# MCU_Signals.net
KiCad netlist of a schematic drawn in Altium Designer
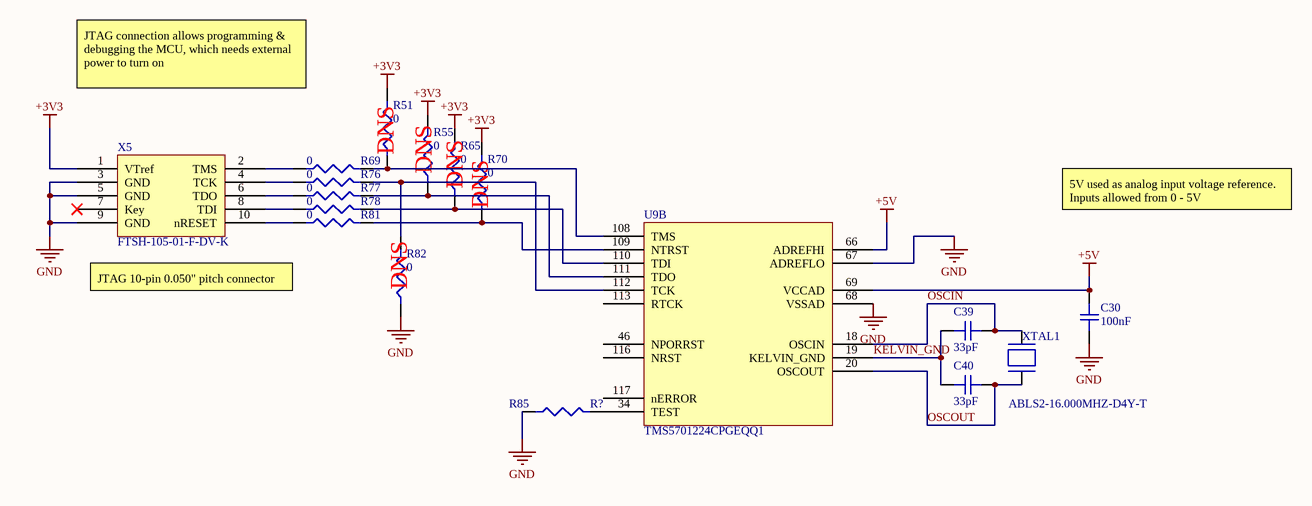
[diagram p0: MCU_Signals.SchDoc]

(export (version "E")
  (design (tool "Eeschema 10.0.6"))
  (components
    (comp (ref "C30")
      (value "100nF")
      (footprint "PHANTOM_FOOTPRINTS:C0805")
      (description "MLCC SMD CAP 100nF 10Volts U2J 5%")
      (fields
        (field (name "MANUFACTURER") "Murata")
        (field (name "MANUFACTURER PART NUMBER") "GRM21B7U1A104JA01L")
      )
      (libsource (lib "PHANTOM_LIBRARY") (part "GRM21B7U1A104JA01L"))
    )
    (comp (ref "C39")
      (value "33pF")
      (footprint "C0805")
      (description "33pF 10V Ceramic Capacitor C0G, NP0 0805 (2012 Metric) 0.079\" L x 0.049\" W (2.00mm x 1.25mm)")
      (fields
        (field (name "MANUFACTURER") "Wurth Electronics")
        (field (name "MANUFACTURER PART NUMBER") "885012007003")
      )
      (libsource (lib "PHANTOM_LIBRARY") (part "885012007003"))
    )
    (comp (ref "C40")
      (value "33pF")
      (footprint "C0805")
      (description "33pF 10V Ceramic Capacitor C0G, NP0 0805 (2012 Metric) 0.079\" L x 0.049\" W (2.00mm x 1.25mm)")
      (fields
        (field (name "MANUFACTURER") "Wurth Electronics")
        (field (name "MANUFACTURER PART NUMBER") "885012007003")
      )
      (libsource (lib "PHANTOM_LIBRARY") (part "885012007003"))
    )
    (comp (ref "R51")
      (value "0")
      (footprint "R0805")
      (description "RES SMD 0 OHM 1/8W 0805")
      (fields
        (field (name "MANUFACTURER") "Yageo")
        (field (name "MANUFACTURER PART NUMBER") "RC0805JR-070RL")
      )
      (libsource (lib "PHANTOM_LIBRARY") (part "RC0805JR-070RL"))
    )
    (comp (ref "R55")
      (value "0")
      (footprint "R0805")
      (description "RES SMD 0 OHM 1/8W 0805")
      (fields
        (field (name "MANUFACTURER") "Yageo")
        (field (name "MANUFACTURER PART NUMBER") "RC0805JR-070RL")
      )
      (libsource (lib "PHANTOM_LIBRARY") (part "RC0805JR-070RL"))
    )
    (comp (ref "R65")
      (value "0")
      (footprint "R0805")
      (description "RES SMD 0 OHM 1/8W 0805")
      (fields
        (field (name "MANUFACTURER") "Yageo")
        (field (name "MANUFACTURER PART NUMBER") "RC0805JR-070RL")
      )
      (libsource (lib "PHANTOM_LIBRARY") (part "RC0805JR-070RL"))
    )
    (comp (ref "R69")
      (value "0")
      (footprint "R0805")
      (description "RES SMD 0 OHM 1/8W 0805")
      (fields
        (field (name "MANUFACTURER") "Yageo")
        (field (name "MANUFACTURER PART NUMBER") "RC0805JR-070RL")
      )
      (libsource (lib "PHANTOM_LIBRARY") (part "RC0805JR-070RL"))
    )
    (comp (ref "R70")
      (value "0")
      (footprint "R0805")
      (description "RES SMD 0 OHM 1/8W 0805")
      (fields
        (field (name "MANUFACTURER") "Yageo")
        (field (name "MANUFACTURER PART NUMBER") "RC0805JR-070RL")
      )
      (libsource (lib "PHANTOM_LIBRARY") (part "RC0805JR-070RL"))
    )
    (comp (ref "R76")
      (value "0")
      (footprint "R0805")
      (description "RES SMD 0 OHM 1/8W 0805")
      (fields
        (field (name "MANUFACTURER") "Yageo")
        (field (name "MANUFACTURER PART NUMBER") "RC0805JR-070RL")
      )
      (libsource (lib "PHANTOM_LIBRARY") (part "RC0805JR-070RL"))
    )
    (comp (ref "R77")
      (value "0")
      (footprint "R0805")
      (description "RES SMD 0 OHM 1/8W 0805")
      (fields
        (field (name "MANUFACTURER") "Yageo")
        (field (name "MANUFACTURER PART NUMBER") "RC0805JR-070RL")
      )
      (libsource (lib "PHANTOM_LIBRARY") (part "RC0805JR-070RL"))
    )
    (comp (ref "R78")
      (value "0")
      (footprint "R0805")
      (description "RES SMD 0 OHM 1/8W 0805")
      (fields
        (field (name "MANUFACTURER") "Yageo")
        (field (name "MANUFACTURER PART NUMBER") "RC0805JR-070RL")
      )
      (libsource (lib "PHANTOM_LIBRARY") (part "RC0805JR-070RL"))
    )
    (comp (ref "R81")
      (value "0")
      (footprint "R0805")
      (description "RES SMD 0 OHM 1/8W 0805")
      (fields
        (field (name "MANUFACTURER") "Yageo")
        (field (name "MANUFACTURER PART NUMBER") "RC0805JR-070RL")
      )
      (libsource (lib "PHANTOM_LIBRARY") (part "RC0805JR-070RL"))
    )
    (comp (ref "R82")
      (value "0")
      (footprint "R0805")
      (description "RES SMD 0 OHM 1/8W 0805")
      (fields
        (field (name "MANUFACTURER") "Yageo")
        (field (name "MANUFACTURER PART NUMBER") "RC0805JR-070RL")
      )
      (libsource (lib "PHANTOM_LIBRARY") (part "RC0805JR-070RL"))
    )
    (comp (ref "R85")
      (value "R?")
      (footprint "R0805")
      (description "RES SMD 2.2K OHM 5% 1/8W")
      (fields
        (field (name "MANUFACTURER") "Yageo")
        (field (name "MANUFACTURER PART NUMBER") "RC0805JR-072K2L")
      )
      (libsource (lib "PHANTOM_LIBRARY") (part "RC0805JR-072K2L"))
    )
    (comp (ref "U9")
      (value "TMS5701224CPGEQQ1")
      (footprint "LQFP-144")
      (description "ARM CORTEX R4 LOCK STEP HERCULES MCU")
      (fields (field (name "MANUFACTURER") "Texas Instruments"))
      (libsource (lib "PHANTOM_LIBRARY") (part "TMS5701224CPGEQQ1"))
    )
    (comp (ref "X5")
      (value "FTSH-105-01-F-DV-K")
      (description ".050 Connector Dual Header 10 Position Surface Mount")
      (fields (field (name "MANUFACTURER") "Samtec"))
      (libsource (lib "PHANTOM_LIBRARY") (part "FTSH-105-01-F-DV-K"))
    )
    (comp (ref "XTAL1")
      (value "ABLS2-16.000MHZ-D4Y-T")
      (footprint "XTAL")
      (description "16MHz ±30ppm Crystal 18pF 40 Ohm -40°C ~ 85°C  Surface Mount HC49/US")
      (fields (field (name "MANUFACTURER") "Abracon") (field (name "TOLERANCE") "30ppm"))
      (libsource (lib "PHANTOM_LIBRARY") (part "ABLS2-16.000MHZ-D4Y-T"))
    )
  )
  (nets
    (net (code "1") (name "+3V3") (class "Default")
      (node (ref "R51") (pin "2") (pinfunction "2_2") (pintype "passive"))
      (node (ref "R55") (pin "2") (pinfunction "2_2") (pintype "passive"))
      (node (ref "R65") (pin "2") (pinfunction "2_2") (pintype "passive"))
      (node (ref "R70") (pin "2") (pinfunction "2_2") (pintype "passive"))
      (node (ref "X5") (pin "1") (pinfunction "VTref_1") (pintype "passive"))
    )
    (net (code "2") (name "+5V") (class "Default")
      (node (ref "C30") (pin "2") (pinfunction "2_2") (pintype "passive"))
      (node (ref "U9") (pin "66") (pinfunction "ADREFHI_66") (pintype "passive"))
      (node (ref "U9") (pin "69") (pinfunction "VCCAD_69") (pintype "passive"))
    )
    (net (code "3") (name "/KELVIN_GND") (class "Default")
      (node (ref "C39") (pin "1") (pinfunction "1_1") (pintype "passive"))
      (node (ref "C40") (pin "1") (pinfunction "1_1") (pintype "passive"))
      (node (ref "U9") (pin "19") (pinfunction "KELVIN_GND_19") (pintype "passive"))
    )
    (net (code "4") (name "/OSCIN") (class "Default")
      (node (ref "C39") (pin "2") (pinfunction "2_2") (pintype "passive"))
      (node (ref "U9") (pin "18") (pinfunction "OSCIN_18") (pintype "passive"))
      (node (ref "XTAL1") (pin "1") (pintype "passive"))
    )
    (net (code "5") (name "/OSCOUT") (class "Default")
      (node (ref "C40") (pin "2") (pinfunction "2_2") (pintype "passive"))
      (node (ref "U9") (pin "20") (pinfunction "OSCOUT_20") (pintype "passive"))
      (node (ref "XTAL1") (pin "2") (pintype "passive"))
    )
    (net (code "6") (name "GND") (class "Default")
      (node (ref "C30") (pin "1") (pinfunction "1_1") (pintype "passive"))
      (node (ref "R82") (pin "1") (pinfunction "1_1") (pintype "passive"))
      (node (ref "R85") (pin "1") (pinfunction "1_1") (pintype "passive"))
      (node (ref "U9") (pin "67") (pinfunction "ADREFLO_67") (pintype "passive"))
      (node (ref "U9") (pin "68") (pinfunction "VSSAD_68") (pintype "passive"))
      (node (ref "X5") (pin "3") (pinfunction "GND_3") (pintype "passive"))
      (node (ref "X5") (pin "5") (pinfunction "GND_5") (pintype "passive"))
      (node (ref "X5") (pin "9") (pinfunction "GND_9") (pintype "passive"))
    )
    (net (code "7") (name "Net-(U9B-NTRST)") (class "Default")
      (node (ref "R70") (pin "1") (pinfunction "1_1") (pintype "passive"))
      (node (ref "R81") (pin "2") (pinfunction "2_2") (pintype "passive"))
      (node (ref "U9") (pin "109") (pinfunction "NTRST_109") (pintype "passive"))
    )
    (net (code "8") (name "Net-(U9B-TCK)") (class "Default")
      (node (ref "R76") (pin "2") (pinfunction "2_2") (pintype "passive"))
      (node (ref "R82") (pin "2") (pinfunction "2_2") (pintype "passive"))
      (node (ref "U9") (pin "112") (pinfunction "TCK_112") (pintype "passive"))
    )
    (net (code "9") (name "Net-(U9B-TDI)") (class "Default")
      (node (ref "R65") (pin "1") (pinfunction "1_1") (pintype "passive"))
      (node (ref "R78") (pin "2") (pinfunction "2_2") (pintype "passive"))
      (node (ref "U9") (pin "110") (pinfunction "TDI_110") (pintype "passive"))
    )
    (net (code "10") (name "Net-(U9B-TDO)") (class "Default")
      (node (ref "R55") (pin "1") (pinfunction "1_1") (pintype "passive"))
      (node (ref "R77") (pin "2") (pinfunction "2_2") (pintype "passive"))
      (node (ref "U9") (pin "111") (pinfunction "TDO_111") (pintype "passive"))
    )
    (net (code "11") (name "Net-(U9B-TEST)") (class "Default")
      (node (ref "R85") (pin "2") (pinfunction "2_2") (pintype "passive"))
      (node (ref "U9") (pin "34") (pinfunction "TEST_34") (pintype "passive"))
    )
    (net (code "12") (name "Net-(U9B-TMS)") (class "Default")
      (node (ref "R51") (pin "1") (pinfunction "1_1") (pintype "passive"))
      (node (ref "R69") (pin "2") (pinfunction "2_2") (pintype "passive"))
      (node (ref "U9") (pin "108") (pinfunction "TMS_108") (pintype "passive"))
    )
    (net (code "13") (name "Net-(X5-TCK)") (class "Default")
      (node (ref "R76") (pin "1") (pinfunction "1_1") (pintype "passive"))
      (node (ref "X5") (pin "4") (pinfunction "TCK_4") (pintype "passive"))
    )
    (net (code "14") (name "Net-(X5-TDI)") (class "Default")
      (node (ref "R78") (pin "1") (pinfunction "1_1") (pintype "passive"))
      (node (ref "X5") (pin "8") (pinfunction "TDI_8") (pintype "passive"))
    )
    (net (code "15") (name "Net-(X5-TDO)") (class "Default")
      (node (ref "R77") (pin "1") (pinfunction "1_1") (pintype "passive"))
      (node (ref "X5") (pin "6") (pinfunction "TDO_6") (pintype "passive"))
    )
    (net (code "16") (name "Net-(X5-TMS)") (class "Default")
      (node (ref "R69") (pin "1") (pinfunction "1_1") (pintype "passive"))
      (node (ref "X5") (pin "2") (pinfunction "TMS_2") (pintype "passive"))
    )
    (net (code "17") (name "Net-(X5-nRESET)") (class "Default")
      (node (ref "R81") (pin "1") (pinfunction "1_1") (pintype "passive"))
      (node (ref "X5") (pin "10") (pinfunction "nRESET_10") (pintype "passive"))
    )
    (net (code "18") (name "unconnected-(U9B-NPORRST-Pad46)") (class "Default")
      (node (ref "U9") (pin "46") (pinfunction "NPORRST_46") (pintype "passive"))
    )
    (net (code "19") (name "unconnected-(U9B-NRST-Pad116)") (class "Default")
      (node (ref "U9") (pin "116") (pinfunction "NRST_116") (pintype "passive"))
    )
    (net (code "20") (name "unconnected-(U9B-RTCK-Pad113)") (class "Default")
      (node (ref "U9") (pin "113") (pinfunction "RTCK_113") (pintype "passive"))
    )
    (net (code "21") (name "unconnected-(U9B-nERROR-Pad117)") (class "Default")
      (node (ref "U9") (pin "117") (pinfunction "nERROR_117") (pintype "passive"))
    )
    (net (code "22") (name "unconnected-(X5-Key-Pad7)") (class "Default")
      (node (ref "X5") (pin "7") (pinfunction "Key_7") (pintype "passive+no_connect"))
    )
  )
)
